# motor.net
KiCad netlist of a schematic drawn in EAGLE
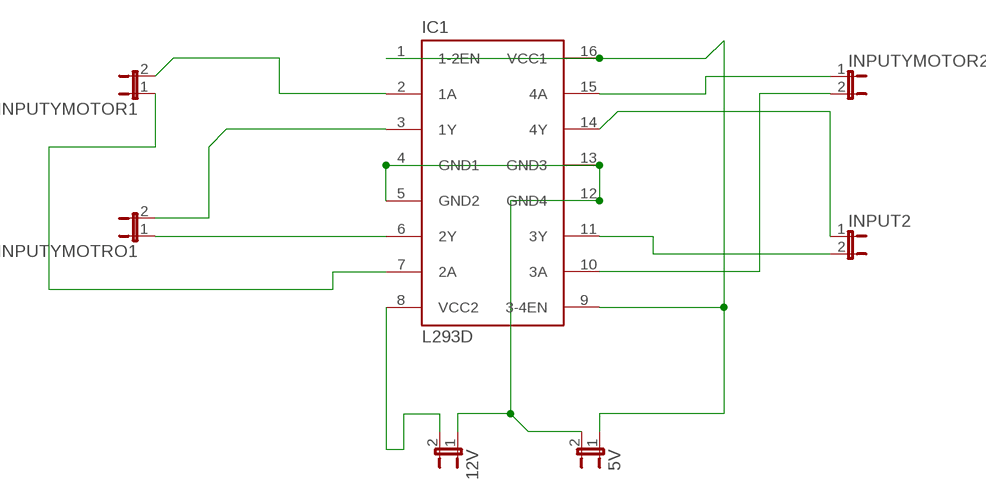
[diagram p0: schematic, sheet 1]

(export (version "E")
  (design (tool "Eeschema 10.0.6"))
  (components
    (comp (ref "5V")
      (value "JP1E")
      (footprint "eagle-import:JP1")
      (libsource (lib "eagle-import") (part "JP1E"))
    )
    (comp (ref "12V")
      (value "JP1E")
      (footprint "eagle-import:JP1")
      (libsource (lib "eagle-import") (part "JP1E"))
    )
    (comp (ref "IC1")
      (value "L293D")
      (footprint "eagle-import:DIL16")
      (libsource (lib "eagle-import") (part "L293D"))
    )
    (comp (ref "INPUT2")
      (value "JP1E")
      (footprint "eagle-import:JP1")
      (libsource (lib "eagle-import") (part "JP1E"))
    )
    (comp (ref "INPUTYMOTOR1")
      (value "JP1E")
      (footprint "eagle-import:JP1")
      (libsource (lib "eagle-import") (part "JP1E"))
    )
    (comp (ref "INPUTYMOTOR2")
      (value "JP1E")
      (footprint "eagle-import:JP1")
      (libsource (lib "eagle-import") (part "JP1E"))
    )
    (comp (ref "INPUTYMOTRO1")
      (value "JP1E")
      (footprint "eagle-import:JP1")
      (libsource (lib "eagle-import") (part "JP1E"))
    )
  )
  (nets
    (net (code "1") (name "Net-(IC1-1-2EN)") (class "Default")
      (node (ref "5V") (pin "1") (pinfunction "1_1") (pintype "passive"))
      (node (ref "IC1") (pin "1") (pinfunction "1-2EN_1") (pintype "input"))
      (node (ref "IC1") (pin "16") (pinfunction "VCC1_16") (pintype "power_in"))
      (node (ref "IC1") (pin "9") (pinfunction "3-4EN_9") (pintype "input"))
    )
    (net (code "2") (name "Net-(IC1-1A)") (class "Default")
      (node (ref "IC1") (pin "2") (pinfunction "1A_2") (pintype "input"))
      (node (ref "INPUTYMOTOR1") (pin "2") (pinfunction "2_2") (pintype "passive"))
    )
    (net (code "3") (name "Net-(IC1-1Y)") (class "Default")
      (node (ref "IC1") (pin "3") (pinfunction "1Y_3") (pintype "output"))
      (node (ref "INPUTYMOTRO1") (pin "2") (pinfunction "2_2") (pintype "passive"))
    )
    (net (code "4") (name "Net-(IC1-2A)") (class "Default")
      (node (ref "IC1") (pin "7") (pinfunction "2A_7") (pintype "input"))
      (node (ref "INPUTYMOTOR1") (pin "1") (pinfunction "1_1") (pintype "passive"))
    )
    (net (code "5") (name "Net-(IC1-2Y)") (class "Default")
      (node (ref "IC1") (pin "6") (pinfunction "2Y_6") (pintype "output"))
      (node (ref "INPUTYMOTRO1") (pin "1") (pinfunction "1_1") (pintype "passive"))
    )
    (net (code "6") (name "Net-(IC1-3A)") (class "Default")
      (node (ref "IC1") (pin "10") (pinfunction "3A_10") (pintype "input"))
      (node (ref "INPUTYMOTOR2") (pin "2") (pinfunction "2_2") (pintype "passive"))
    )
    (net (code "7") (name "Net-(IC1-3Y)") (class "Default")
      (node (ref "IC1") (pin "11") (pinfunction "3Y_11") (pintype "output"))
      (node (ref "INPUT2") (pin "2") (pinfunction "2_2") (pintype "passive"))
    )
    (net (code "8") (name "Net-(IC1-4A)") (class "Default")
      (node (ref "IC1") (pin "15") (pinfunction "4A_15") (pintype "input"))
      (node (ref "INPUTYMOTOR2") (pin "1") (pinfunction "1_1") (pintype "passive"))
    )
    (net (code "9") (name "Net-(IC1-4Y)") (class "Default")
      (node (ref "IC1") (pin "14") (pinfunction "4Y_14") (pintype "output"))
      (node (ref "INPUT2") (pin "1") (pinfunction "1_1") (pintype "passive"))
    )
    (net (code "10") (name "Net-(IC1-GND1)") (class "Default")
      (node (ref "12V") (pin "1") (pinfunction "1_1") (pintype "passive"))
      (node (ref "5V") (pin "2") (pinfunction "2_2") (pintype "passive"))
      (node (ref "IC1") (pin "12") (pinfunction "GND4_12") (pintype "power_in"))
      (node (ref "IC1") (pin "13") (pinfunction "GND3_13") (pintype "power_in"))
      (node (ref "IC1") (pin "4") (pinfunction "GND1_4") (pintype "power_in"))
      (node (ref "IC1") (pin "5") (pinfunction "GND2_5") (pintype "power_in"))
    )
    (net (code "11") (name "Net-(IC1-VCC2)") (class "Default")
      (node (ref "12V") (pin "2") (pinfunction "2_2") (pintype "passive"))
      (node (ref "IC1") (pin "8") (pinfunction "VCC2_8") (pintype "power_in"))
    )
  )
)
